# Sensors.net
KiCad netlist of a schematic drawn in Altium Designer
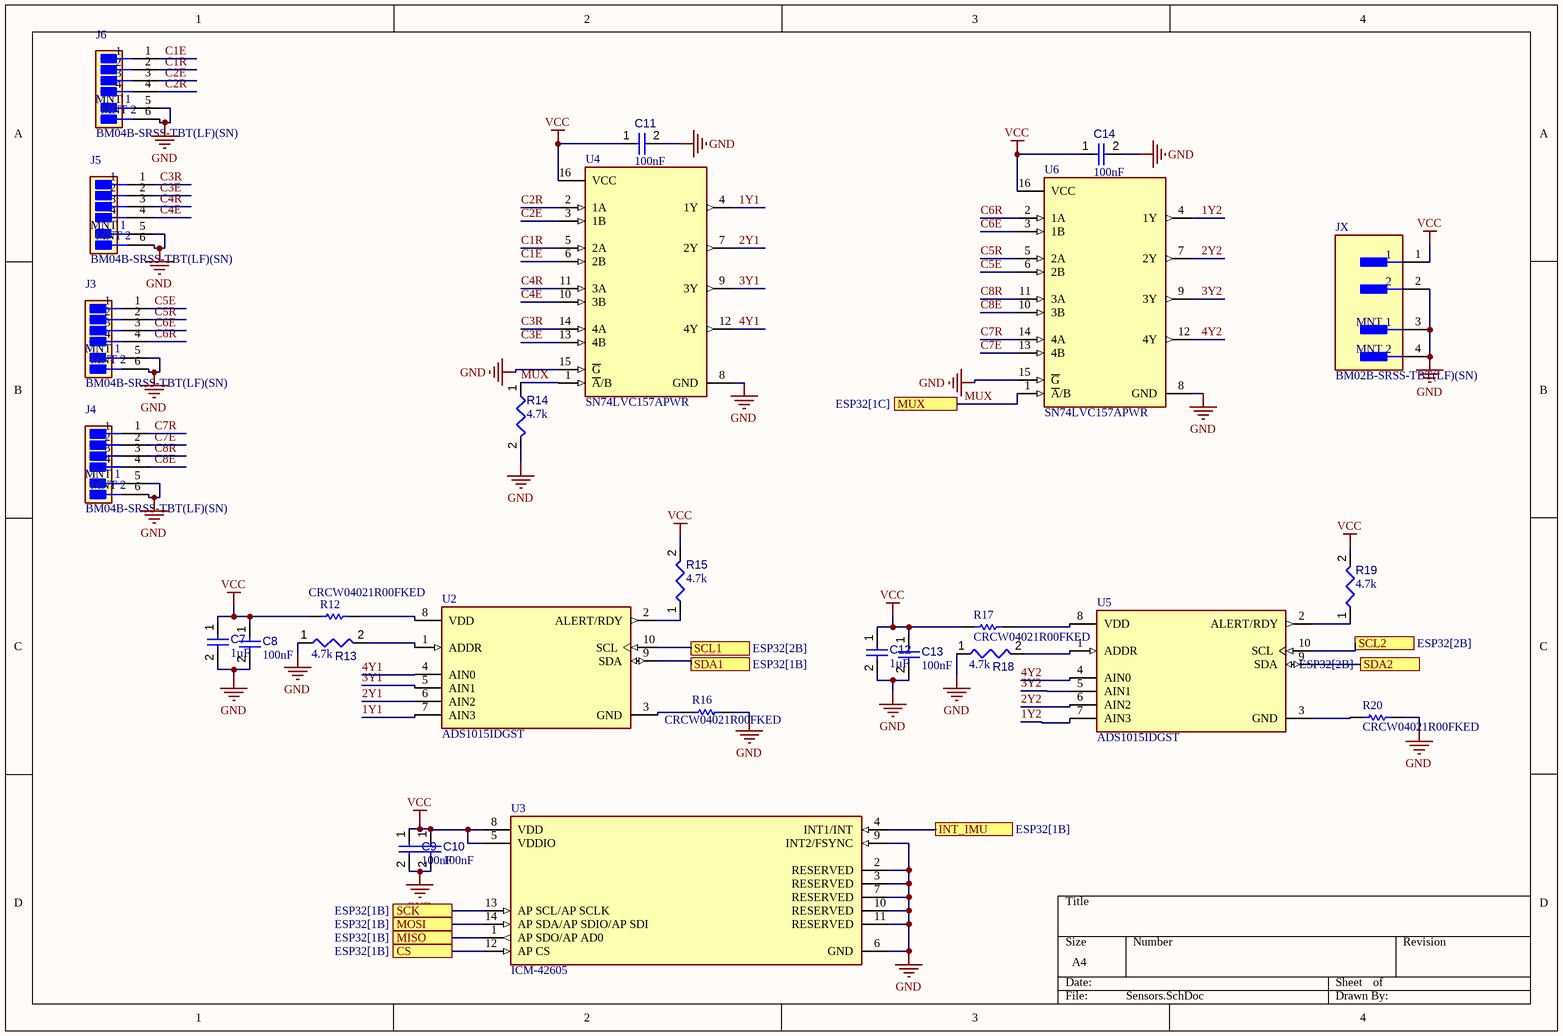
[diagram p0: Sensors.SchDoc]

(export (version "E")
  (design (tool "Eeschema 10.0.6"))
  (components
    (comp (ref "C7")
      (value "1µF")
      (footprint "CAPC1005X55X25LL05T10")
      (description "Chip Capacitor, 1 uF, +/- 10%, 6.3 V, 0402 (1005 Metric)")
      (fields (field (name "TOLERANCE") "10%") (field (name "Comment") "Capacitor 1 uF +/- 10% 6.3 V 0402"))
      (libsource (lib "Own Worskpace") (part "CAP-NP-2"))
    )
    (comp (ref "C8")
      (value "100nF")
      (footprint "CAPC1005X56X25LL10T15")
      (description "Chip Capacitor, 0.1 uF, +/- 5%, 16 V, 0402 (1005 Metric)")
      (fields (field (name "TOLERANCE") "5%") (field (name "Comment") "Capacitor 0.1 uF +/- 5% 16 V 0402"))
      (libsource (lib "Own Worskpace") (part "CAP-NP-2"))
    )
    (comp (ref "C9")
      (value "100nF")
      (footprint "CAPC1005X56X25LL10T15")
      (description "Chip Capacitor, 0.1 uF, +/- 5%, 16 V, 0402 (1005 Metric)")
      (fields (field (name "TOLERANCE") "5%") (field (name "Comment") "Capacitor 0.1 uF +/- 5% 16 V 0402"))
      (libsource (lib "Own Worskpace") (part "CAP-NP-2"))
    )
    (comp (ref "C10")
      (value "100nF")
      (footprint "CAPC1005X56X25LL10T15")
      (description "Chip Capacitor, 0.1 uF, +/- 5%, 16 V, 0402 (1005 Metric)")
      (fields (field (name "TOLERANCE") "5%") (field (name "Comment") "Capacitor 0.1 uF +/- 5% 16 V 0402"))
      (libsource (lib "Own Worskpace") (part "CAP-NP-2"))
    )
    (comp (ref "C11")
      (value "100nF")
      (footprint "CAPC1005X56X25LL10T15")
      (description "Chip Capacitor, 0.1 uF, +/- 5%, 16 V, 0402 (1005 Metric)")
      (fields (field (name "TOLERANCE") "5%") (field (name "Comment") "Capacitor 0.1 uF +/- 5% 16 V 0402"))
      (libsource (lib "Own Worskpace") (part "CAP-NP-2"))
    )
    (comp (ref "C12")
      (value "1µF")
      (footprint "CAPC1005X55X25LL05T10")
      (description "Chip Capacitor, 1 uF, +/- 10%, 6.3 V, 0402 (1005 Metric)")
      (fields (field (name "TOLERANCE") "10%") (field (name "Comment") "Capacitor 1 uF +/- 10% 6.3 V 0402"))
      (libsource (lib "Own Worskpace") (part "CAP-NP-2"))
    )
    (comp (ref "C13")
      (value "100nF")
      (footprint "CAPC1005X56X25LL10T15")
      (description "Chip Capacitor, 0.1 uF, +/- 5%, 16 V, 0402 (1005 Metric)")
      (fields (field (name "TOLERANCE") "5%") (field (name "Comment") "Capacitor 0.1 uF +/- 5% 16 V 0402"))
      (libsource (lib "Own Worskpace") (part "CAP-NP-2"))
    )
    (comp (ref "C14")
      (value "100nF")
      (footprint "CAPC1005X56X25LL10T15")
      (description "Chip Capacitor, 0.1 uF, +/- 5%, 16 V, 0402 (1005 Metric)")
      (fields (field (name "TOLERANCE") "5%") (field (name "Comment") "Capacitor 0.1 uF +/- 5% 16 V 0402"))
      (libsource (lib "Own Worskpace") (part "CAP-NP-2"))
    )
    (comp (ref "J3")
      (value "BM04B-SRSS-TBT(LF)(SN)")
      (footprint "FP-BM04B-SRSS-TBT_LF_SN-MFG")
      (description "1.0mm Pitch, Ultra-Compact, Low Profile Design, Interchangeable Shrouded Header")
      (libsource (lib "Own Worskpace") (part "8e3688c4b118bffc0dd9b7401e414ba"))
    )
    (comp (ref "J4")
      (value "BM04B-SRSS-TBT(LF)(SN)")
      (footprint "FP-BM04B-SRSS-TBT_LF_SN-MFG")
      (description "1.0mm Pitch, Ultra-Compact, Low Profile Design, Interchangeable Shrouded Header")
      (libsource (lib "Own Worskpace") (part "8e3688c4b118bffc0dd9b7401e414ba"))
    )
    (comp (ref "J5")
      (value "BM04B-SRSS-TBT(LF)(SN)")
      (footprint "FP-BM04B-SRSS-TBT_LF_SN-MFG")
      (description "1.0mm Pitch, Ultra-Compact, Low Profile Design, Interchangeable Shrouded Header")
      (libsource (lib "Own Worskpace") (part "8e3688c4b118bffc0dd9b7401e414ba"))
    )
    (comp (ref "J6")
      (value "BM04B-SRSS-TBT(LF)(SN)")
      (footprint "FP-BM04B-SRSS-TBT_LF_SN-MFG")
      (description "1.0mm Pitch, Ultra-Compact, Low Profile Design, Interchangeable Shrouded Header")
      (libsource (lib "Own Worskpace") (part "8e3688c4b118bffc0dd9b7401e414ba"))
    )
    (comp (ref "JX")
      (value "BM02B-SRSS-TBT(LF)(SN)")
      (footprint "FP-BM02B-SRSS-TBT_LF_SN-MFG")
      (description "CONN WIRE HDR 2POS 1MM STSMD")
      (libsource (lib "Altium Content Vault") (part "029478cb6d4f2fad0cd2a245525ee6d"))
    )
    (comp (ref "R12")
      (value "CRCW04021R00FKED")
      (footprint "RESC1005X40X25ML05T05")
      (fields (field (name "MANUFACTURER") "Vishay Dale"))
      (libsource (lib "Altium Content Vault") (part "RES"))
    )
    (comp (ref "R13")
      (value "4.7k")
      (footprint "RESC1005X40X25ML05T05")
      (description "Chip Resistor, 4.7 KOhm, +/- 1%, 0.1 W, -55 to 155 degC, 0402 (1005 Metric)")
      (fields (field (name "POWER") "100mW") (field (name "TOLERANCE") "1%"))
      (libsource (lib "Own Worskpace") (part "RES-2"))
    )
    (comp (ref "R14")
      (value "4.7k")
      (footprint "RESC1005X40X25ML05T05")
      (description "Chip Resistor, 4.7 KOhm, +/- 1%, 0.1 W, -55 to 155 degC, 0402 (1005 Metric)")
      (fields (field (name "POWER") "100mW") (field (name "TOLERANCE") "1%"))
      (libsource (lib "Own Worskpace") (part "RES-2"))
    )
    (comp (ref "R15")
      (value "4.7k")
      (footprint "RESC1005X40X25ML05T05")
      (description "Chip Resistor, 4.7 KOhm, +/- 1%, 0.1 W, -55 to 155 degC, 0402 (1005 Metric)")
      (fields (field (name "POWER") "100mW") (field (name "TOLERANCE") "1%"))
      (libsource (lib "Own Worskpace") (part "RES-2"))
    )
    (comp (ref "R16")
      (value "CRCW04021R00FKED")
      (footprint "RESC1005X40X25ML05T05")
      (fields (field (name "MANUFACTURER") "Vishay Dale"))
      (libsource (lib "Altium Content Vault") (part "RES"))
    )
    (comp (ref "R17")
      (value "CRCW04021R00FKED")
      (footprint "RESC1005X40X25ML05T05")
      (fields (field (name "MANUFACTURER") "Vishay Dale"))
      (libsource (lib "Altium Content Vault") (part "RES"))
    )
    (comp (ref "R18")
      (value "4.7k")
      (footprint "RESC1005X40X25ML05T05")
      (description "Chip Resistor, 4.7 KOhm, +/- 1%, 0.1 W, -55 to 155 degC, 0402 (1005 Metric)")
      (fields (field (name "POWER") "100mW") (field (name "TOLERANCE") "1%"))
      (libsource (lib "Own Worskpace") (part "RES-2"))
    )
    (comp (ref "R19")
      (value "4.7k")
      (footprint "RESC1005X40X25ML05T05")
      (description "Chip Resistor, 4.7 KOhm, +/- 1%, 0.1 W, -55 to 155 degC, 0402 (1005 Metric)")
      (fields (field (name "POWER") "100mW") (field (name "TOLERANCE") "1%"))
      (libsource (lib "Own Worskpace") (part "RES-2"))
    )
    (comp (ref "R20")
      (value "CRCW04021R00FKED")
      (footprint "RESC1005X40X25ML05T05")
      (fields (field (name "MANUFACTURER") "Vishay Dale"))
      (libsource (lib "Altium Content Vault") (part "RES"))
    )
    (comp (ref "U2")
      (value "ADS1015IDGST")
      (footprint "FP-DGS0010A-MFG")
      (description "IC ADC 12BIT SIGMA-DELTA 10VSSOP")
      (libsource (lib "Altium Content Vault") (part "0fb225032f4bd54fd540a872e776a50"))
    )
    (comp (ref "U3")
      (value "ICM-42605")
      (footprint "FP-ICM-42605-MFG")
      (description "Open-drain, CMOS, 14 Pin")
      (libsource (lib "Own Worskpace") (part "bbc3dc4f710ccfa7c9c43d4e109f75e"))
    )
    (comp (ref "U4")
      (value "SN74LVC157APWR")
      (footprint "FP-PW0016A-IPC_B")
      (description "Multiplexer, LVC/LCX/Z Series, 4-Func, 2 Line Input, 1 Line Output, True Output, CMOS, PDSO16")
      (libsource (lib "Own Worskpace") (part "8ed77614c0d039494a56e65624d96c5"))
    )
    (comp (ref "U5")
      (value "ADS1015IDGST")
      (footprint "FP-DGS0010A-MFG")
      (description "IC ADC 12BIT SIGMA-DELTA 10VSSOP")
      (libsource (lib "Altium Content Vault") (part "0fb225032f4bd54fd540a872e776a50"))
    )
    (comp (ref "U6")
      (value "SN74LVC157APWR")
      (footprint "FP-PW0016A-IPC_B")
      (description "Multiplexer, LVC/LCX/Z Series, 4-Func, 2 Line Input, 1 Line Output, True Output, CMOS, PDSO16")
      (libsource (lib "Own Worskpace") (part "8ed77614c0d039494a56e65624d96c5"))
    )
  )
  (nets
    (net (code "1") (name "/1Y1") (class "Default")
      (node (ref "U2") (pin "7") (pinfunction "AIN3_7") (pintype "passive"))
      (node (ref "U4") (pin "4") (pinfunction "1Y_4") (pintype "output"))
    )
    (net (code "2") (name "/1Y2") (class "Default")
      (node (ref "U5") (pin "7") (pinfunction "AIN3_7") (pintype "passive"))
      (node (ref "U6") (pin "4") (pinfunction "1Y_4") (pintype "output"))
    )
    (net (code "3") (name "/2Y1") (class "Default")
      (node (ref "U2") (pin "6") (pinfunction "AIN2_6") (pintype "passive"))
      (node (ref "U4") (pin "7") (pinfunction "2Y_7") (pintype "output"))
    )
    (net (code "4") (name "/2Y2") (class "Default")
      (node (ref "U5") (pin "6") (pinfunction "AIN2_6") (pintype "passive"))
      (node (ref "U6") (pin "7") (pinfunction "2Y_7") (pintype "output"))
    )
    (net (code "5") (name "/3Y1") (class "Default")
      (node (ref "U2") (pin "5") (pinfunction "AIN1_5") (pintype "passive"))
      (node (ref "U4") (pin "9") (pinfunction "3Y_9") (pintype "output"))
    )
    (net (code "6") (name "/3Y2") (class "Default")
      (node (ref "U5") (pin "5") (pinfunction "AIN1_5") (pintype "passive"))
      (node (ref "U6") (pin "9") (pinfunction "3Y_9") (pintype "output"))
    )
    (net (code "7") (name "/4Y1") (class "Default")
      (node (ref "U2") (pin "4") (pinfunction "AIN0_4") (pintype "passive"))
      (node (ref "U4") (pin "12") (pinfunction "4Y_12") (pintype "output"))
    )
    (net (code "8") (name "/4Y2") (class "Default")
      (node (ref "U5") (pin "4") (pinfunction "AIN0_4") (pintype "passive"))
      (node (ref "U6") (pin "12") (pinfunction "4Y_12") (pintype "output"))
    )
    (net (code "9") (name "/C1E") (class "Default")
      (node (ref "J6") (pin "1") (pinfunction "1_1") (pintype "passive"))
      (node (ref "U4") (pin "6") (pinfunction "2B_6") (pintype "input"))
    )
    (net (code "10") (name "/C1R") (class "Default")
      (node (ref "J6") (pin "2") (pinfunction "2_2") (pintype "passive"))
      (node (ref "U4") (pin "5") (pinfunction "2A_5") (pintype "input"))
    )
    (net (code "11") (name "/C2E") (class "Default")
      (node (ref "J6") (pin "3") (pinfunction "3_3") (pintype "passive"))
      (node (ref "U4") (pin "3") (pinfunction "1B_3") (pintype "input"))
    )
    (net (code "12") (name "/C2R") (class "Default")
      (node (ref "J6") (pin "4") (pinfunction "4_4") (pintype "passive"))
      (node (ref "U4") (pin "2") (pinfunction "1A_2") (pintype "input"))
    )
    (net (code "13") (name "/C3E") (class "Default")
      (node (ref "J5") (pin "2") (pinfunction "2_2") (pintype "passive"))
      (node (ref "U4") (pin "13") (pinfunction "4B_13") (pintype "input"))
    )
    (net (code "14") (name "/C3R") (class "Default")
      (node (ref "J5") (pin "1") (pinfunction "1_1") (pintype "passive"))
      (node (ref "U4") (pin "14") (pinfunction "4A_14") (pintype "input"))
    )
    (net (code "15") (name "/C4E") (class "Default")
      (node (ref "J5") (pin "4") (pinfunction "4_4") (pintype "passive"))
      (node (ref "U4") (pin "10") (pinfunction "3B_10") (pintype "input"))
    )
    (net (code "16") (name "/C4R") (class "Default")
      (node (ref "J5") (pin "3") (pinfunction "3_3") (pintype "passive"))
      (node (ref "U4") (pin "11") (pinfunction "3A_11") (pintype "input"))
    )
    (net (code "17") (name "/C5E") (class "Default")
      (node (ref "J3") (pin "1") (pinfunction "1_1") (pintype "passive"))
      (node (ref "U6") (pin "6") (pinfunction "2B_6") (pintype "input"))
    )
    (net (code "18") (name "/C5R") (class "Default")
      (node (ref "J3") (pin "2") (pinfunction "2_2") (pintype "passive"))
      (node (ref "U6") (pin "5") (pinfunction "2A_5") (pintype "input"))
    )
    (net (code "19") (name "/C6E") (class "Default")
      (node (ref "J3") (pin "3") (pinfunction "3_3") (pintype "passive"))
      (node (ref "U6") (pin "3") (pinfunction "1B_3") (pintype "input"))
    )
    (net (code "20") (name "/C6R") (class "Default")
      (node (ref "J3") (pin "4") (pinfunction "4_4") (pintype "passive"))
      (node (ref "U6") (pin "2") (pinfunction "1A_2") (pintype "input"))
    )
    (net (code "21") (name "/C7E") (class "Default")
      (node (ref "J4") (pin "2") (pinfunction "2_2") (pintype "passive"))
      (node (ref "U6") (pin "13") (pinfunction "4B_13") (pintype "input"))
    )
    (net (code "22") (name "/C7R") (class "Default")
      (node (ref "J4") (pin "1") (pinfunction "1_1") (pintype "passive"))
      (node (ref "U6") (pin "14") (pinfunction "4A_14") (pintype "input"))
    )
    (net (code "23") (name "/C8E") (class "Default")
      (node (ref "J4") (pin "4") (pinfunction "4_4") (pintype "passive"))
      (node (ref "U6") (pin "10") (pinfunction "3B_10") (pintype "input"))
    )
    (net (code "24") (name "/C8R") (class "Default")
      (node (ref "J4") (pin "3") (pinfunction "3_3") (pintype "passive"))
      (node (ref "U6") (pin "11") (pinfunction "3A_11") (pintype "input"))
    )
    (net (code "25") (name "/CS") (class "Default")
      (node (ref "U3") (pin "12") (pinfunction "AP_CS_12") (pintype "input"))
    )
    (net (code "26") (name "/INT_IMU") (class "Default")
      (node (ref "U3") (pin "4") (pinfunction "INT1/INT_4") (pintype "input"))
    )
    (net (code "27") (name "/MISO") (class "Default")
      (node (ref "U3") (pin "1") (pinfunction "AP_SDO/AP_AD0_1") (pintype "output"))
    )
    (net (code "28") (name "/MOSI") (class "Default")
      (node (ref "U3") (pin "14") (pinfunction "AP_SDA/AP_SDIO/AP_SDI_14") (pintype "input"))
    )
    (net (code "29") (name "/MUX") (class "Default")
      (node (ref "R14") (pin "1") (pinfunction "1_1") (pintype "passive"))
      (node (ref "U4") (pin "1") (pinfunction "~{A}/B_1") (pintype "input"))
      (node (ref "U6") (pin "1") (pinfunction "~{A}/B_1") (pintype "input"))
    )
    (net (code "30") (name "/SCK") (class "Default")
      (node (ref "U3") (pin "13") (pinfunction "AP_SCL/AP_SCLK_13") (pintype "input"))
    )
    (net (code "31") (name "/SCL1") (class "Default")
      (node (ref "U2") (pin "10") (pinfunction "SCL_10") (pintype "input"))
    )
    (net (code "32") (name "/SCL2") (class "Default")
      (node (ref "U5") (pin "10") (pinfunction "SCL_10") (pintype "input"))
    )
    (net (code "33") (name "/SDA1") (class "Default")
      (node (ref "U2") (pin "9") (pinfunction "SDA_9") (pintype "bidirectional"))
    )
    (net (code "34") (name "/SDA2") (class "Default")
      (node (ref "U5") (pin "9") (pinfunction "SDA_9") (pintype "bidirectional"))
    )
    (net (code "35") (name "GND") (class "Default")
      (node (ref "C10") (pin "2") (pinfunction "2_2") (pintype "passive"))
      (node (ref "C11") (pin "2") (pinfunction "2_2") (pintype "passive"))
      (node (ref "C12") (pin "2") (pinfunction "2_2") (pintype "passive"))
      (node (ref "C13") (pin "2") (pinfunction "2_2") (pintype "passive"))
      (node (ref "C14") (pin "2") (pinfunction "2_2") (pintype "passive"))
      (node (ref "C7") (pin "2") (pinfunction "2_2") (pintype "passive"))
      (node (ref "C8") (pin "2") (pinfunction "2_2") (pintype "passive"))
      (node (ref "C9") (pin "2") (pinfunction "2_2") (pintype "passive"))
      (node (ref "J3") (pin "5") (pinfunction "MNT_1_5") (pintype "passive"))
      (node (ref "J3") (pin "6") (pinfunction "MNT_2_6") (pintype "passive"))
      (node (ref "J4") (pin "5") (pinfunction "MNT_1_5") (pintype "passive"))
      (node (ref "J4") (pin "6") (pinfunction "MNT_2_6") (pintype "passive"))
      (node (ref "J5") (pin "5") (pinfunction "MNT_1_5") (pintype "passive"))
      (node (ref "J5") (pin "6") (pinfunction "MNT_2_6") (pintype "passive"))
      (node (ref "J6") (pin "5") (pinfunction "MNT_1_5") (pintype "passive"))
      (node (ref "J6") (pin "6") (pinfunction "MNT_2_6") (pintype "passive"))
      (node (ref "JX") (pin "2") (pinfunction "2_2") (pintype "passive"))
      (node (ref "JX") (pin "3") (pinfunction "MNT_1_3") (pintype "passive"))
      (node (ref "JX") (pin "4") (pinfunction "MNT_2_4") (pintype "passive"))
      (node (ref "R13") (pin "1") (pinfunction "1_1") (pintype "passive"))
      (node (ref "R14") (pin "2") (pinfunction "2_2") (pintype "passive"))
      (node (ref "R16") (pin "2") (pinfunction "2_2") (pintype "passive"))
      (node (ref "R18") (pin "1") (pinfunction "1_1") (pintype "passive"))
      (node (ref "R20") (pin "2") (pinfunction "2_2") (pintype "passive"))
      (node (ref "U3") (pin "10") (pinfunction "RESERVED_10") (pintype "passive"))
      (node (ref "U3") (pin "11") (pinfunction "RESERVED_11") (pintype "passive"))
      (node (ref "U3") (pin "2") (pinfunction "RESERVED_2") (pintype "passive"))
      (node (ref "U3") (pin "3") (pinfunction "RESERVED_3") (pintype "passive"))
      (node (ref "U3") (pin "6") (pinfunction "GND_6") (pintype "power_in"))
      (node (ref "U3") (pin "7") (pinfunction "RESERVED_7") (pintype "passive"))
      (node (ref "U3") (pin "9") (pinfunction "INT2/FSYNC_9") (pintype "input"))
      (node (ref "U4") (pin "15") (pinfunction "~{G}_15") (pintype "input"))
      (node (ref "U4") (pin "8") (pinfunction "GND_8") (pintype "power_in"))
      (node (ref "U6") (pin "15") (pinfunction "~{G}_15") (pintype "input"))
      (node (ref "U6") (pin "8") (pinfunction "GND_8") (pintype "power_in"))
    )
    (net (code "36") (name "Net-(U2-ADDR)") (class "Default")
      (node (ref "R13") (pin "2") (pinfunction "2_2") (pintype "passive"))
      (node (ref "U2") (pin "1") (pinfunction "ADDR_1") (pintype "input"))
    )
    (net (code "37") (name "Net-(U2-ALERT{slash}RDY)") (class "Default")
      (node (ref "R15") (pin "1") (pinfunction "1_1") (pintype "passive"))
      (node (ref "U2") (pin "2") (pinfunction "ALERT/RDY_2") (pintype "output"))
    )
    (net (code "38") (name "Net-(U2-GND)") (class "Default")
      (node (ref "R16") (pin "1") (pinfunction "1_1") (pintype "passive"))
      (node (ref "U2") (pin "3") (pinfunction "GND_3") (pintype "power_in"))
    )
    (net (code "39") (name "Net-(U2-VDD)") (class "Default")
      (node (ref "R12") (pin "2") (pinfunction "2_2") (pintype "passive"))
      (node (ref "U2") (pin "8") (pinfunction "VDD_8") (pintype "power_in"))
    )
    (net (code "40") (name "Net-(U5-ADDR)") (class "Default")
      (node (ref "R18") (pin "2") (pinfunction "2_2") (pintype "passive"))
      (node (ref "U5") (pin "1") (pinfunction "ADDR_1") (pintype "input"))
    )
    (net (code "41") (name "Net-(U5-ALERT{slash}RDY)") (class "Default")
      (node (ref "R19") (pin "1") (pinfunction "1_1") (pintype "passive"))
      (node (ref "U5") (pin "2") (pinfunction "ALERT/RDY_2") (pintype "output"))
    )
    (net (code "42") (name "Net-(U5-GND)") (class "Default")
      (node (ref "R20") (pin "1") (pinfunction "1_1") (pintype "passive"))
      (node (ref "U5") (pin "3") (pinfunction "GND_3") (pintype "power_in"))
    )
    (net (code "43") (name "Net-(U5-VDD)") (class "Default")
      (node (ref "R17") (pin "2") (pinfunction "2_2") (pintype "passive"))
      (node (ref "U5") (pin "8") (pinfunction "VDD_8") (pintype "power_in"))
    )
    (net (code "44") (name "VCC") (class "Default")
      (node (ref "C10") (pin "1") (pinfunction "1_1") (pintype "passive"))
      (node (ref "C11") (pin "1") (pinfunction "1_1") (pintype "passive"))
      (node (ref "C12") (pin "1") (pinfunction "1_1") (pintype "passive"))
      (node (ref "C13") (pin "1") (pinfunction "1_1") (pintype "passive"))
      (node (ref "C14") (pin "1") (pinfunction "1_1") (pintype "passive"))
      (node (ref "C7") (pin "1") (pinfunction "1_1") (pintype "passive"))
      (node (ref "C8") (pin "1") (pinfunction "1_1") (pintype "passive"))
      (node (ref "C9") (pin "1") (pinfunction "1_1") (pintype "passive"))
      (node (ref "JX") (pin "1") (pinfunction "1_1") (pintype "passive"))
      (node (ref "R12") (pin "1") (pinfunction "1_1") (pintype "passive"))
      (node (ref "R15") (pin "2") (pinfunction "2_2") (pintype "passive"))
      (node (ref "R17") (pin "1") (pinfunction "1_1") (pintype "passive"))
      (node (ref "R19") (pin "2") (pinfunction "2_2") (pintype "passive"))
      (node (ref "U3") (pin "5") (pinfunction "VDDIO_5") (pintype "power_in"))
      (node (ref "U3") (pin "8") (pinfunction "VDD_8") (pintype "power_in"))
      (node (ref "U4") (pin "16") (pinfunction "VCC_16") (pintype "power_in"))
      (node (ref "U6") (pin "16") (pinfunction "VCC_16") (pintype "power_in"))
    )
  )
)
